# keytar-knob.net
KiCad netlist of a schematic drawn in EAGLE
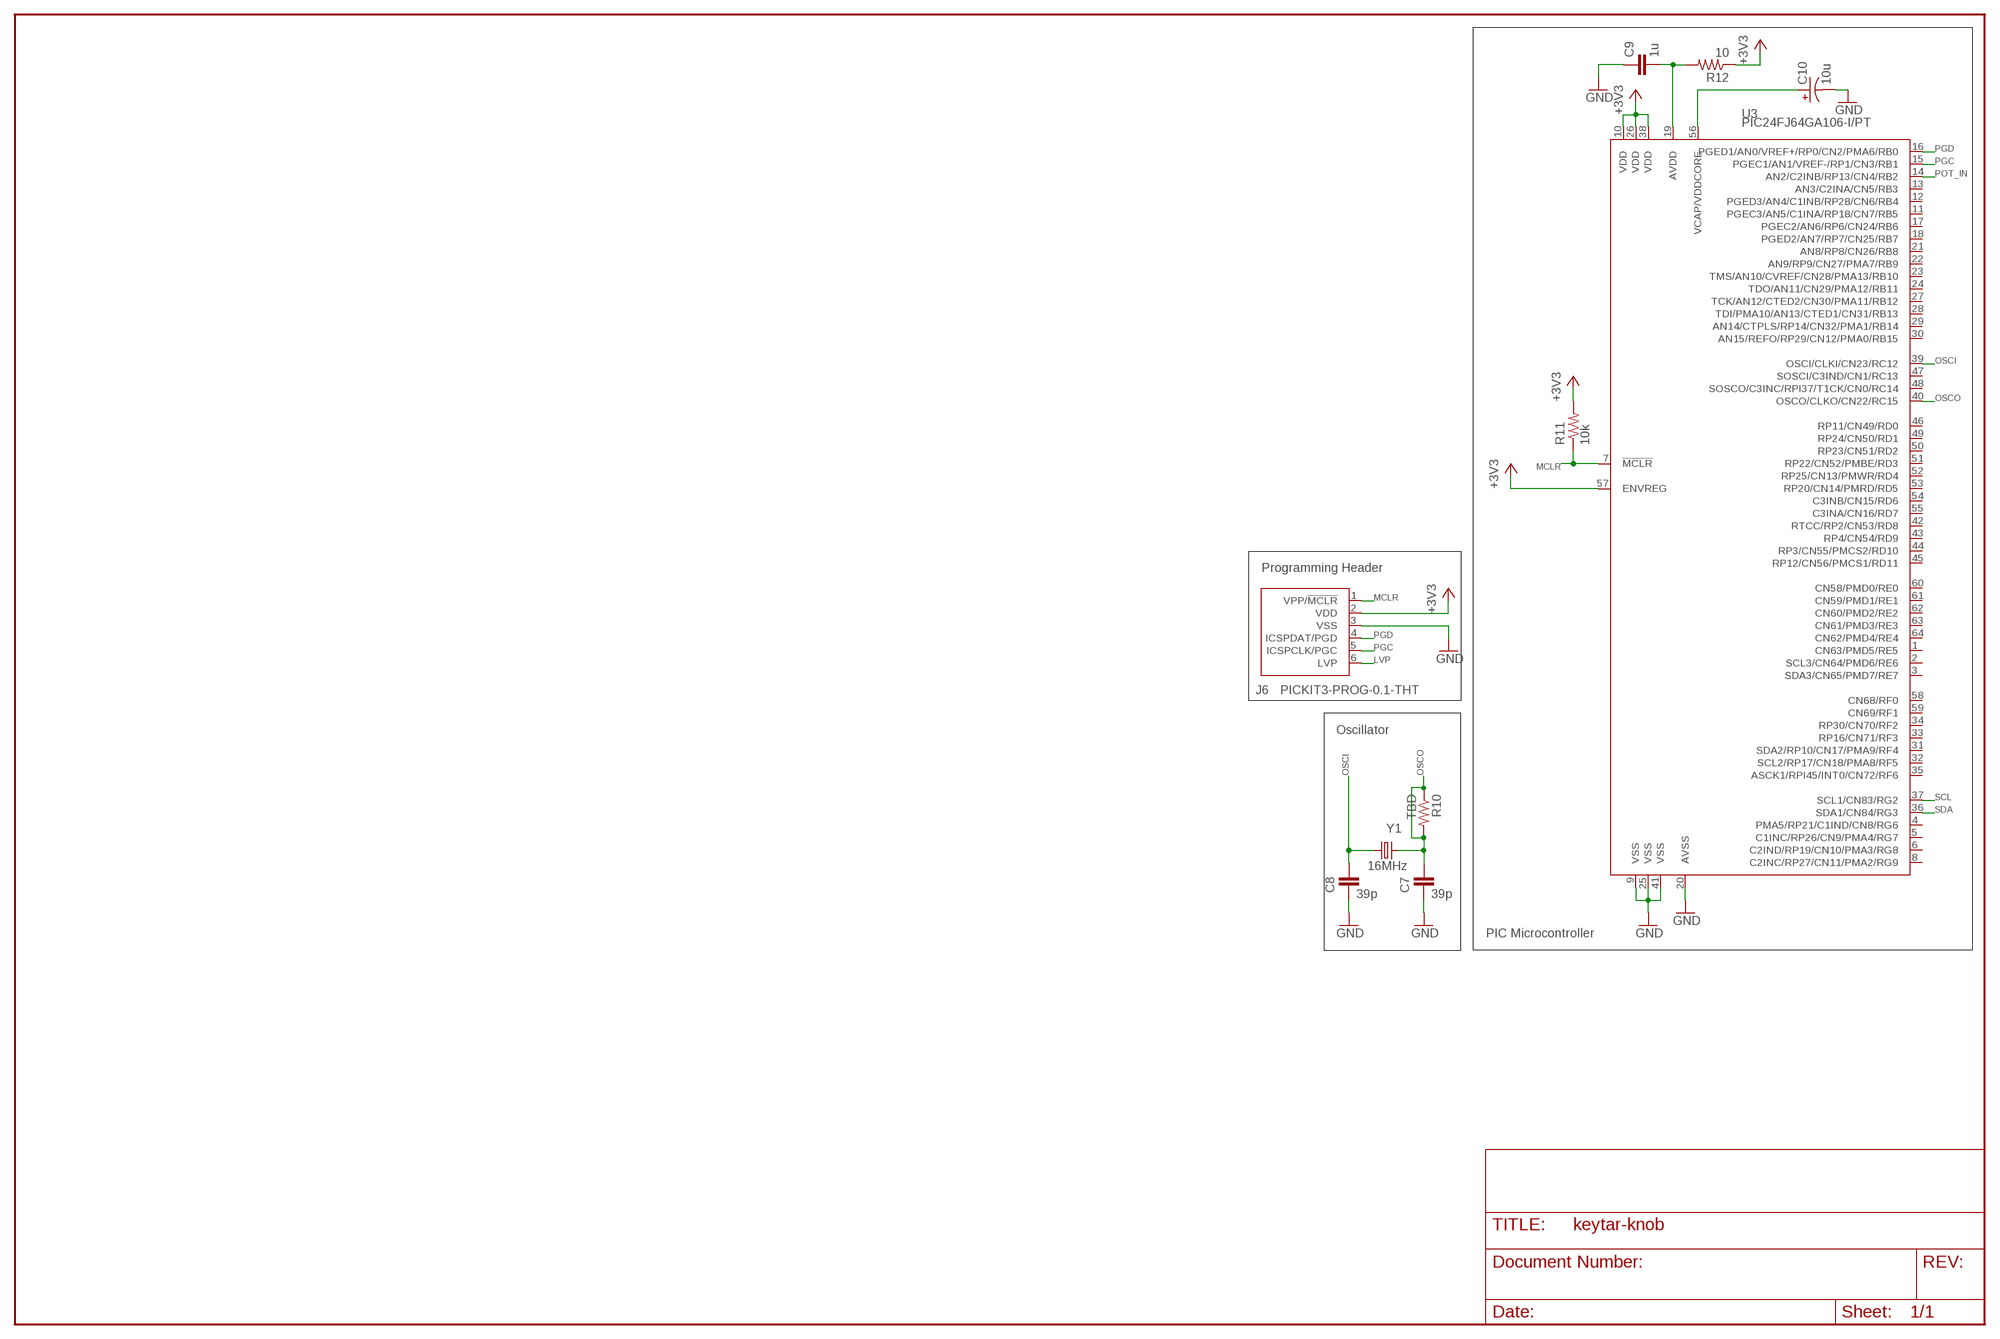
[diagram p0: schematic, sheet 1]

(export (version "E")
  (design (tool "Eeschema 10.0.6"))
  (components
    (comp (ref "C7")
      (value "39p")
      (footprint "eagle-import:C0603")
      (libsource (lib "eagle-import") (part "C0603"))
    )
    (comp (ref "C8")
      (value "39p")
      (footprint "eagle-import:C0603")
      (libsource (lib "eagle-import") (part "C0603"))
    )
    (comp (ref "C9")
      (value "1u")
      (footprint "eagle-import:C0603")
      (libsource (lib "eagle-import") (part "C0603"))
    )
    (comp (ref "C10")
      (value "10u")
      (footprint "eagle-import:AVX-CAP-N")
      (libsource (lib "eagle-import") (part "AVX-CAP-N"))
    )
    (comp (ref "J6")
      (value "PICKIT3-PROG-0.1-THT")
      (footprint "eagle-import:HEADER-0.1-6")
      (libsource (lib "eagle-import") (part "PICKIT3-PROG-0.1-THT"))
    )
    (comp (ref "R10")
      (value "TBD")
      (footprint "eagle-import:R0603")
      (libsource (lib "eagle-import") (part "R0603"))
    )
    (comp (ref "R11")
      (value "10k")
      (footprint "eagle-import:R0603")
      (libsource (lib "eagle-import") (part "R0603"))
    )
    (comp (ref "R12")
      (value "10")
      (footprint "eagle-import:R0603")
      (libsource (lib "eagle-import") (part "R0603"))
    )
    (comp (ref "U3")
      (value "PIC24FJ64GA106-I/PT")
      (footprint "eagle-import:QFP50P1200X1200X120-64N")
      (libsource (lib "eagle-import") (part "PIC24FJ64GA106-I/PT"))
    )
    (comp (ref "Y1")
      (value "16MHz")
      (footprint "eagle-import:CRYSTAL-SMD-4")
      (libsource (lib "eagle-import") (part "CRYSTAL-SMD-4"))
    )
  )
  (nets
    (net (code "1") (name "+3V3") (class "Default")
      (node (ref "J6") (pin "2") (pinfunction "VDD_2") (pintype "passive"))
      (node (ref "R11") (pin "2") (pinfunction "2_2") (pintype "passive"))
      (node (ref "R12") (pin "1") (pinfunction "1_1") (pintype "passive"))
      (node (ref "U3") (pin "10") (pinfunction "VDD_10") (pintype "passive"))
      (node (ref "U3") (pin "26") (pinfunction "VDD_26") (pintype "passive"))
      (node (ref "U3") (pin "38") (pinfunction "VDD_38") (pintype "passive"))
      (node (ref "U3") (pin "57") (pinfunction "ENVREG_57") (pintype "passive"))
    )
    (net (code "2") (name "GND") (class "Default")
      (node (ref "C10") (pin "C") (pinfunction "C_C") (pintype "passive"))
      (node (ref "C7") (pin "2") (pinfunction "2_2") (pintype "passive"))
      (node (ref "C8") (pin "2") (pinfunction "2_2") (pintype "passive"))
      (node (ref "C9") (pin "1") (pinfunction "1_1") (pintype "passive"))
      (node (ref "J6") (pin "3") (pinfunction "VSS_3") (pintype "passive"))
      (node (ref "U3") (pin "20") (pinfunction "AVSS_20") (pintype "passive"))
      (node (ref "U3") (pin "25") (pinfunction "VSS_25") (pintype "passive"))
      (node (ref "U3") (pin "41") (pinfunction "VSS_41") (pintype "passive"))
      (node (ref "U3") (pin "9") (pinfunction "VSS_9") (pintype "passive"))
    )
    (net (code "3") (name "LVP") (class "Default")
      (node (ref "J6") (pin "6") (pinfunction "LVP_6") (pintype "passive"))
    )
    (net (code "4") (name "MCLR") (class "Default")
      (node (ref "J6") (pin "1") (pinfunction "VPP/~{MCLR}_1") (pintype "passive"))
      (node (ref "R11") (pin "1") (pinfunction "1_1") (pintype "passive"))
      (node (ref "U3") (pin "7") (pinfunction "~{MCLR}_7") (pintype "passive"))
    )
    (net (code "5") (name "Net-(U3-AVDD)") (class "Default")
      (node (ref "C9") (pin "2") (pinfunction "2_2") (pintype "passive"))
      (node (ref "R12") (pin "2") (pinfunction "2_2") (pintype "passive"))
      (node (ref "U3") (pin "19") (pinfunction "AVDD_19") (pintype "passive"))
    )
    (net (code "6") (name "Net-(U3-VCAP{slash}VDDCORE)") (class "Default")
      (node (ref "C10") (pin "A") (pinfunction "A_A") (pintype "passive"))
      (node (ref "U3") (pin "56") (pinfunction "VCAP/VDDCORE_56") (pintype "passive"))
    )
    (net (code "7") (name "OSCI") (class "Default")
      (node (ref "C8") (pin "1") (pinfunction "1_1") (pintype "passive"))
      (node (ref "U3") (pin "39") (pinfunction "OSCI/CLKI/CN23/RC12_39") (pintype "passive"))
      (node (ref "Y1") (pin "1") (pinfunction "1_1") (pintype "passive"))
    )
    (net (code "8") (name "OSCO") (class "Default")
      (node (ref "C7") (pin "1") (pinfunction "1_1") (pintype "passive"))
      (node (ref "R10") (pin "1") (pinfunction "1_1") (pintype "passive"))
      (node (ref "R10") (pin "2") (pinfunction "2_2") (pintype "passive"))
      (node (ref "U3") (pin "40") (pinfunction "OSCO/CLKO/CN22/RC15_40") (pintype "passive"))
      (node (ref "Y1") (pin "3") (pinfunction "2_3") (pintype "passive"))
    )
    (net (code "9") (name "PGC") (class "Default")
      (node (ref "J6") (pin "5") (pinfunction "ICSPCLK/PGC_5") (pintype "passive"))
      (node (ref "U3") (pin "15") (pinfunction "PGEC1/AN1/VREF-/RP1/CN3/RB1_15") (pintype "passive"))
    )
    (net (code "10") (name "PGD") (class "Default")
      (node (ref "J6") (pin "4") (pinfunction "ICSPDAT/PGD_4") (pintype "passive"))
      (node (ref "U3") (pin "16") (pinfunction "PGED1/AN0/VREF+/RP0/CN2/PMA6/RB0_16") (pintype "passive"))
    )
    (net (code "11") (name "POT_IN") (class "Default")
      (node (ref "U3") (pin "14") (pinfunction "AN2/C2INB/RP13/CN4/RB2_14") (pintype "passive"))
    )
    (net (code "12") (name "SCL") (class "Default")
      (node (ref "U3") (pin "37") (pinfunction "SCL1/CN83/RG2_37") (pintype "passive"))
    )
    (net (code "13") (name "SDA") (class "Default")
      (node (ref "U3") (pin "36") (pinfunction "SDA1/CN84/RG3_36") (pintype "passive"))
    )
    (net (code "14") (name "unconnected-(U3-AN3{slash}C2INA{slash}CN5{slash}RB3-Pad13)") (class "Default")
      (node (ref "U3") (pin "13") (pinfunction "AN3/C2INA/CN5/RB3_13") (pintype "passive"))
    )
    (net (code "15") (name "unconnected-(U3-AN8{slash}RP8{slash}CN26{slash}RB8-Pad21)") (class "Default")
      (node (ref "U3") (pin "21") (pinfunction "AN8/RP8/CN26/RB8_21") (pintype "passive"))
    )
    (net (code "16") (name "unconnected-(U3-AN9{slash}RP9{slash}CN27{slash}PMA7{slash}RB9-Pad22)") (class "Default")
      (node (ref "U3") (pin "22") (pinfunction "AN9/RP9/CN27/PMA7/RB9_22") (pintype "passive"))
    )
    (net (code "17") (name "unconnected-(U3-AN14{slash}CTPLS{slash}RP14{slash}CN32{slash}PMA1{slash}RB14-Pad29)") (class "Default")
      (node (ref "U3") (pin "29") (pinfunction "AN14/CTPLS/RP14/CN32/PMA1/RB14_29") (pintype "passive"))
    )
    (net (code "18") (name "unconnected-(U3-AN15{slash}REFO{slash}RP29{slash}CN12{slash}PMA0{slash}RB15-Pad30)") (class "Default")
      (node (ref "U3") (pin "30") (pinfunction "AN15/REFO/RP29/CN12/PMA0/RB15_30") (pintype "passive"))
    )
    (net (code "19") (name "unconnected-(U3-ASCK1{slash}RPI45{slash}INT0{slash}CN72{slash}RF6-Pad35)") (class "Default")
      (node (ref "U3") (pin "35") (pinfunction "ASCK1/RPI45/INT0/CN72/RF6_35") (pintype "passive"))
    )
    (net (code "20") (name "unconnected-(U3-C1INC{slash}RP26{slash}CN9{slash}PMA4{slash}RG7-Pad5)") (class "Default")
      (node (ref "U3") (pin "5") (pinfunction "C1INC/RP26/CN9/PMA4/RG7_5") (pintype "passive"))
    )
    (net (code "21") (name "unconnected-(U3-C2INC{slash}RP27{slash}CN11{slash}PMA2{slash}RG9-Pad8)") (class "Default")
      (node (ref "U3") (pin "8") (pinfunction "C2INC/RP27/CN11/PMA2/RG9_8") (pintype "passive"))
    )
    (net (code "22") (name "unconnected-(U3-C2IND{slash}RP19{slash}CN10{slash}PMA3{slash}RG8-Pad6)") (class "Default")
      (node (ref "U3") (pin "6") (pinfunction "C2IND/RP19/CN10/PMA3/RG8_6") (pintype "passive"))
    )
    (net (code "23") (name "unconnected-(U3-C3INA{slash}CN16{slash}RD7-Pad55)") (class "Default")
      (node (ref "U3") (pin "55") (pinfunction "C3INA/CN16/RD7_55") (pintype "passive"))
    )
    (net (code "24") (name "unconnected-(U3-C3INB{slash}CN15{slash}RD6-Pad54)") (class "Default")
      (node (ref "U3") (pin "54") (pinfunction "C3INB/CN15/RD6_54") (pintype "passive"))
    )
    (net (code "25") (name "unconnected-(U3-CN58{slash}PMD0{slash}RE0-Pad60)") (class "Default")
      (node (ref "U3") (pin "60") (pinfunction "CN58/PMD0/RE0_60") (pintype "passive"))
    )
    (net (code "26") (name "unconnected-(U3-CN59{slash}PMD1{slash}RE1-Pad61)") (class "Default")
      (node (ref "U3") (pin "61") (pinfunction "CN59/PMD1/RE1_61") (pintype "passive"))
    )
    (net (code "27") (name "unconnected-(U3-CN60{slash}PMD2{slash}RE2-Pad62)") (class "Default")
      (node (ref "U3") (pin "62") (pinfunction "CN60/PMD2/RE2_62") (pintype "passive"))
    )
    (net (code "28") (name "unconnected-(U3-CN61{slash}PMD3{slash}RE3-Pad63)") (class "Default")
      (node (ref "U3") (pin "63") (pinfunction "CN61/PMD3/RE3_63") (pintype "passive"))
    )
    (net (code "29") (name "unconnected-(U3-CN62{slash}PMD4{slash}RE4-Pad64)") (class "Default")
      (node (ref "U3") (pin "64") (pinfunction "CN62/PMD4/RE4_64") (pintype "passive"))
    )
    (net (code "30") (name "unconnected-(U3-CN63{slash}PMD5{slash}RE5-Pad1)") (class "Default")
      (node (ref "U3") (pin "1") (pinfunction "CN63/PMD5/RE5_1") (pintype "passive"))
    )
    (net (code "31") (name "unconnected-(U3-CN68{slash}RF0-Pad58)") (class "Default")
      (node (ref "U3") (pin "58") (pinfunction "CN68/RF0_58") (pintype "passive"))
    )
    (net (code "32") (name "unconnected-(U3-CN69{slash}RF1-Pad59)") (class "Default")
      (node (ref "U3") (pin "59") (pinfunction "CN69/RF1_59") (pintype "passive"))
    )
    (net (code "33") (name "unconnected-(U3-PGEC2{slash}AN6{slash}RP6{slash}CN24{slash}RB6-Pad17)") (class "Default")
      (node (ref "U3") (pin "17") (pinfunction "PGEC2/AN6/RP6/CN24/RB6_17") (pintype "passive"))
    )
    (net (code "34") (name "unconnected-(U3-PGEC3{slash}AN5{slash}C1INA{slash}RP18{slash}CN7{slash}RB5-Pad11)") (class "Default")
      (node (ref "U3") (pin "11") (pinfunction "PGEC3/AN5/C1INA/RP18/CN7/RB5_11") (pintype "passive"))
    )
    (net (code "35") (name "unconnected-(U3-PGED2{slash}AN7{slash}RP7{slash}CN25{slash}RB7-Pad18)") (class "Default")
      (node (ref "U3") (pin "18") (pinfunction "PGED2/AN7/RP7/CN25/RB7_18") (pintype "passive"))
    )
    (net (code "36") (name "unconnected-(U3-PGED3{slash}AN4{slash}C1INB{slash}RP28{slash}CN6{slash}RB4-Pad12)") (class "Default")
      (node (ref "U3") (pin "12") (pinfunction "PGED3/AN4/C1INB/RP28/CN6/RB4_12") (pintype "passive"))
    )
    (net (code "37") (name "unconnected-(U3-PMA5{slash}RP21{slash}C1IND{slash}CN8{slash}RG6-Pad4)") (class "Default")
      (node (ref "U3") (pin "4") (pinfunction "PMA5/RP21/C1IND/CN8/RG6_4") (pintype "passive"))
    )
    (net (code "38") (name "unconnected-(U3-RP3{slash}CN55{slash}PMCS2{slash}RD10-Pad44)") (class "Default")
      (node (ref "U3") (pin "44") (pinfunction "RP3/CN55/PMCS2/RD10_44") (pintype "passive"))
    )
    (net (code "39") (name "unconnected-(U3-RP4{slash}CN54{slash}RD9-Pad43)") (class "Default")
      (node (ref "U3") (pin "43") (pinfunction "RP4/CN54/RD9_43") (pintype "passive"))
    )
    (net (code "40") (name "unconnected-(U3-RP11{slash}CN49{slash}RD0-Pad46)") (class "Default")
      (node (ref "U3") (pin "46") (pinfunction "RP11/CN49/RD0_46") (pintype "passive"))
    )
    (net (code "41") (name "unconnected-(U3-RP12{slash}CN56{slash}PMCS1{slash}RD11-Pad45)") (class "Default")
      (node (ref "U3") (pin "45") (pinfunction "RP12/CN56/PMCS1/RD11_45") (pintype "passive"))
    )
    (net (code "42") (name "unconnected-(U3-RP16{slash}CN71{slash}RF3-Pad33)") (class "Default")
      (node (ref "U3") (pin "33") (pinfunction "RP16/CN71/RF3_33") (pintype "passive"))
    )
    (net (code "43") (name "unconnected-(U3-RP20{slash}CN14{slash}PMRD{slash}RD5-Pad53)") (class "Default")
      (node (ref "U3") (pin "53") (pinfunction "RP20/CN14/PMRD/RD5_53") (pintype "passive"))
    )
    (net (code "44") (name "unconnected-(U3-RP22{slash}CN52{slash}PMBE{slash}RD3-Pad51)") (class "Default")
      (node (ref "U3") (pin "51") (pinfunction "RP22/CN52/PMBE/RD3_51") (pintype "passive"))
    )
    (net (code "45") (name "unconnected-(U3-RP23{slash}CN51{slash}RD2-Pad50)") (class "Default")
      (node (ref "U3") (pin "50") (pinfunction "RP23/CN51/RD2_50") (pintype "passive"))
    )
    (net (code "46") (name "unconnected-(U3-RP24{slash}CN50{slash}RD1-Pad49)") (class "Default")
      (node (ref "U3") (pin "49") (pinfunction "RP24/CN50/RD1_49") (pintype "passive"))
    )
    (net (code "47") (name "unconnected-(U3-RP25{slash}CN13{slash}PMWR{slash}RD4-Pad52)") (class "Default")
      (node (ref "U3") (pin "52") (pinfunction "RP25/CN13/PMWR/RD4_52") (pintype "passive"))
    )
    (net (code "48") (name "unconnected-(U3-RP30{slash}CN70{slash}RF2-Pad34)") (class "Default")
      (node (ref "U3") (pin "34") (pinfunction "RP30/CN70/RF2_34") (pintype "passive"))
    )
    (net (code "49") (name "unconnected-(U3-RTCC{slash}RP2{slash}CN53{slash}RD8-Pad42)") (class "Default")
      (node (ref "U3") (pin "42") (pinfunction "RTCC/RP2/CN53/RD8_42") (pintype "passive"))
    )
    (net (code "50") (name "unconnected-(U3-SCL2{slash}RP17{slash}CN18{slash}PMA8{slash}RF5-Pad32)") (class "Default")
      (node (ref "U3") (pin "32") (pinfunction "SCL2/RP17/CN18/PMA8/RF5_32") (pintype "passive"))
    )
    (net (code "51") (name "unconnected-(U3-SCL3{slash}CN64{slash}PMD6{slash}RE6-Pad2)") (class "Default")
      (node (ref "U3") (pin "2") (pinfunction "SCL3/CN64/PMD6/RE6_2") (pintype "passive"))
    )
    (net (code "52") (name "unconnected-(U3-SDA2{slash}RP10{slash}CN17{slash}PMA9{slash}RF4-Pad31)") (class "Default")
      (node (ref "U3") (pin "31") (pinfunction "SDA2/RP10/CN17/PMA9/RF4_31") (pintype "passive"))
    )
    (net (code "53") (name "unconnected-(U3-SDA3{slash}CN65{slash}PMD7{slash}RE7-Pad3)") (class "Default")
      (node (ref "U3") (pin "3") (pinfunction "SDA3/CN65/PMD7/RE7_3") (pintype "passive"))
    )
    (net (code "54") (name "unconnected-(U3-SOSCI{slash}C3IND{slash}CN1{slash}RC13-Pad47)") (class "Default")
      (node (ref "U3") (pin "47") (pinfunction "SOSCI/C3IND/CN1/RC13_47") (pintype "passive"))
    )
    (net (code "55") (name "unconnected-(U3-SOSCO{slash}C3INC{slash}RPI37{slash}T1CK{slash}CN0{slash}RC14-Pad48)") (class "Default")
      (node (ref "U3") (pin "48") (pinfunction "SOSCO/C3INC/RPI37/T1CK/CN0/RC14_48") (pintype "passive"))
    )
    (net (code "56") (name "unconnected-(U3-TCK{slash}AN12{slash}CTED2{slash}CN30{slash}PMA11{slash}RB12-Pad27)") (class "Default")
      (node (ref "U3") (pin "27") (pinfunction "TCK/AN12/CTED2/CN30/PMA11/RB12_27") (pintype "passive"))
    )
    (net (code "57") (name "unconnected-(U3-TDI{slash}PMA10{slash}AN13{slash}CTED1{slash}CN31{slash}RB13-Pad28)") (class "Default")
      (node (ref "U3") (pin "28") (pinfunction "TDI/PMA10/AN13/CTED1/CN31/RB13_28") (pintype "passive"))
    )
    (net (code "58") (name "unconnected-(U3-TDO{slash}AN11{slash}CN29{slash}PMA12{slash}RB11-Pad24)") (class "Default")
      (node (ref "U3") (pin "24") (pinfunction "TDO/AN11/CN29/PMA12/RB11_24") (pintype "passive"))
    )
    (net (code "59") (name "unconnected-(U3-TMS{slash}AN10{slash}CVREF{slash}CN28{slash}PMA13{slash}RB10-Pad23)") (class "Default")
      (node (ref "U3") (pin "23") (pinfunction "TMS/AN10/CVREF/CN28/PMA13/RB10_23") (pintype "passive"))
    )
  )
)
